# Sheet1.net
KiCad netlist of a schematic drawn in Altium Designer
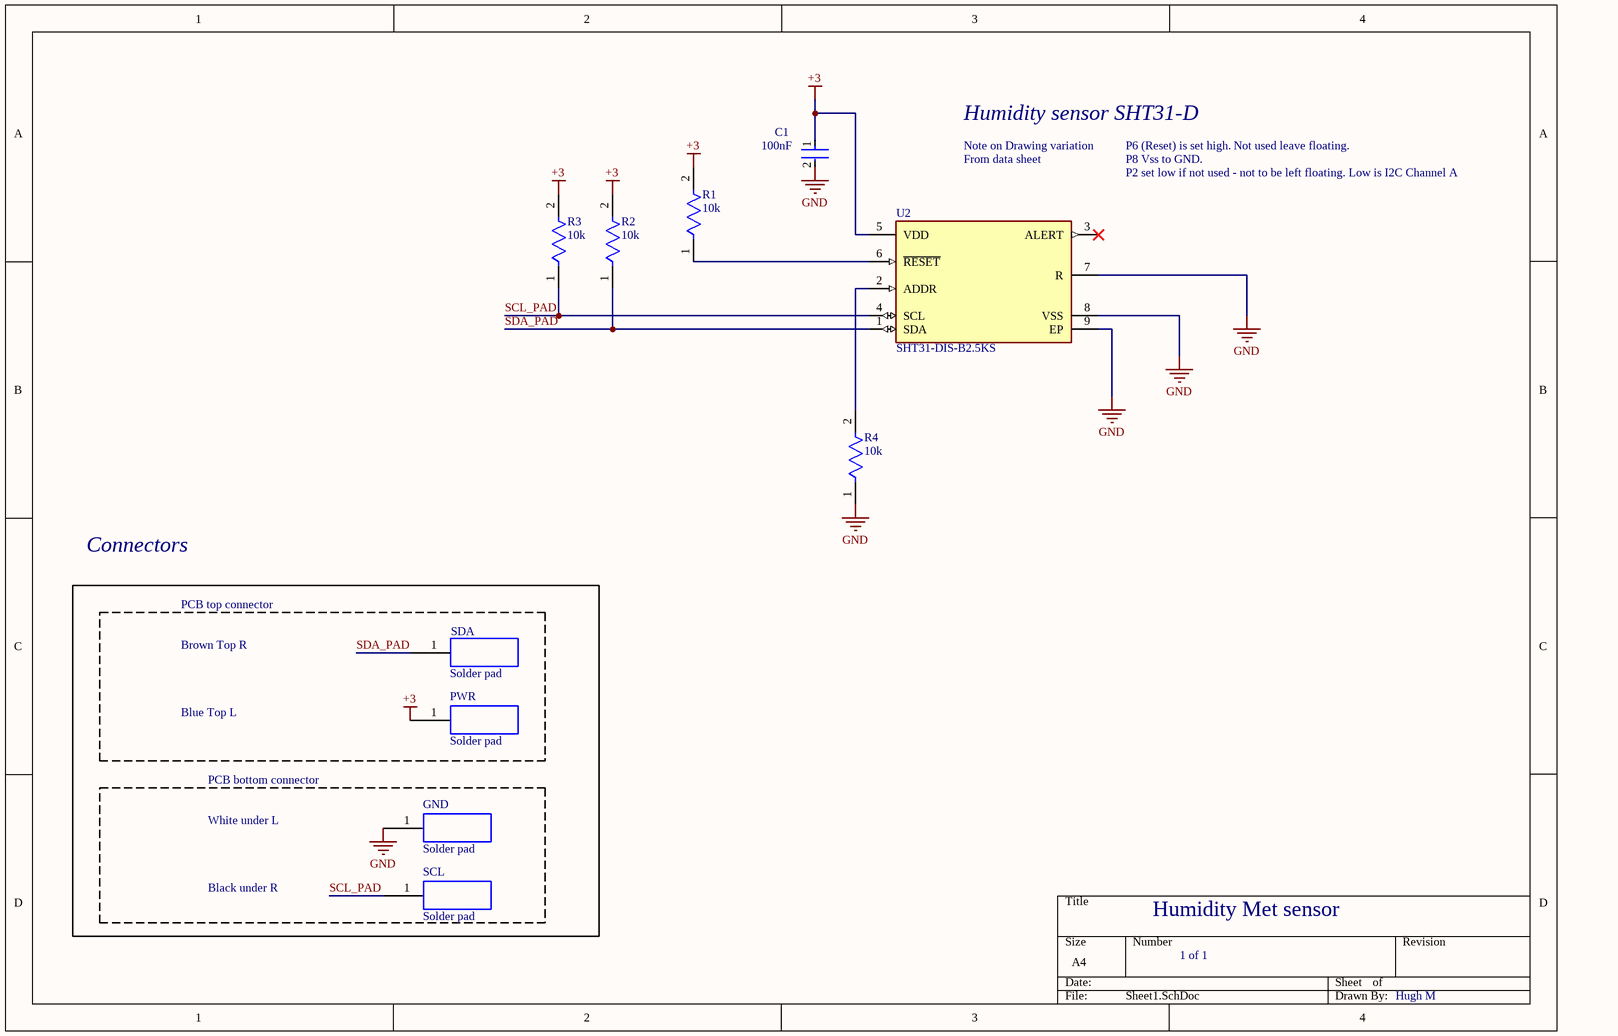
[diagram p0: Sheet1.SchDoc]

(export (version "E")
  (design (tool "Eeschema 10.0.6"))
  (components
    (comp (ref "C1")
      (value "100nF")
      (footprint "FP-C0402-BB-MFG")
      (description "CAP CER 0.1UF 10V X5R 0402")
      (fields (field (name "MANUFACTURER") "Kemet") (field (name "TOLERANCE") "0.1"))
      (libsource (lib "Altium Content Vault") (part "b4654b650e69147ec39a6b967a45e02"))
    )
    (comp (ref "GND") (value "Solder pad") (footprint "pad") (libsource (lib "pad1") (part "pad")))
    (comp (ref "PWR") (value "Solder pad") (footprint "pad") (libsource (lib "pad1") (part "pad")))
    (comp (ref "R1")
      (value "10k")
      (footprint "FP-AC0402-MFG")
      (description "RES 10kΩ ±1% 0.063W 0402")
      (fields (field (name "TOLERANCE") "1%"))
      (libsource (lib "Altium Content Vault") (part "1029c3af85768c4190bb7ad29bc67b5"))
    )
    (comp (ref "R2")
      (value "10k")
      (footprint "FP-AC0402-MFG")
      (description "RES 10kΩ ±1% 0.063W 0402")
      (fields (field (name "TOLERANCE") "1%"))
      (libsource (lib "Altium Content Vault") (part "1029c3af85768c4190bb7ad29bc67b5"))
    )
    (comp (ref "R3")
      (value "10k")
      (footprint "FP-AC0402-MFG")
      (description "RES 10kΩ ±1% 0.063W 0402")
      (fields (field (name "TOLERANCE") "1%"))
      (libsource (lib "Altium Content Vault") (part "1029c3af85768c4190bb7ad29bc67b5"))
    )
    (comp (ref "R4")
      (value "10k")
      (footprint "FP-AC0402-MFG")
      (description "RES 10kΩ ±1% 0.063W 0402")
      (fields (field (name "TOLERANCE") "1%"))
      (libsource (lib "Altium Content Vault") (part "1029c3af85768c4190bb7ad29bc67b5"))
    )
    (comp (ref "SCL") (value "Solder pad") (footprint "pad") (libsource (lib "pad1") (part "pad")))
    (comp (ref "SDA") (value "Solder pad") (footprint "pad") (libsource (lib "pad1") (part "pad")))
    (comp (ref "U2")
      (value "SHT31-DIS-B2.5KS")
      (footprint "FP-SHT31-DIS-B2_5KS-MFG")
      (description "SENSOR HUMID/TEMP 5V I2C 2% SMD")
      (libsource (lib "Altium Content Vault") (part "666307a9354d2867b06523a408f450d"))
    )
  )
  (nets
    (net (code "1") (name "+3") (class "Default")
      (node (ref "C1") (pin "1") (pinfunction "1_1") (pintype "passive"))
      (node (ref "PWR") (pin "1") (pinfunction "1_1") (pintype "passive"))
      (node (ref "R1") (pin "2") (pinfunction "2_2") (pintype "passive"))
      (node (ref "R2") (pin "2") (pinfunction "2_2") (pintype "passive"))
      (node (ref "R3") (pin "2") (pinfunction "2_2") (pintype "passive"))
      (node (ref "U2") (pin "5") (pinfunction "VDD_5") (pintype "power_in"))
    )
    (net (code "2") (name "/SCL_PAD") (class "Default")
      (node (ref "R3") (pin "1") (pinfunction "1_1") (pintype "passive"))
      (node (ref "SCL") (pin "1") (pinfunction "1_1") (pintype "passive"))
      (node (ref "U2") (pin "4") (pinfunction "SCL_4") (pintype "bidirectional"))
    )
    (net (code "3") (name "/SDA_PAD") (class "Default")
      (node (ref "R2") (pin "1") (pinfunction "1_1") (pintype "passive"))
      (node (ref "SDA") (pin "1") (pinfunction "1_1") (pintype "passive"))
      (node (ref "U2") (pin "1") (pinfunction "SDA_1") (pintype "bidirectional"))
    )
    (net (code "4") (name "GND") (class "Default")
      (node (ref "C1") (pin "2") (pinfunction "2_2") (pintype "passive"))
      (node (ref "GND") (pin "1") (pinfunction "1_1") (pintype "passive"))
      (node (ref "R4") (pin "1") (pinfunction "1_1") (pintype "passive"))
      (node (ref "U2") (pin "7") (pinfunction "R_7") (pintype "passive"))
      (node (ref "U2") (pin "8") (pinfunction "VSS_8") (pintype "power_in"))
      (node (ref "U2") (pin "9") (pinfunction "EP_9") (pintype "power_in"))
    )
    (net (code "5") (name "Net-(U2-ADDR)") (class "Default")
      (node (ref "R4") (pin "2") (pinfunction "2_2") (pintype "passive"))
      (node (ref "U2") (pin "2") (pinfunction "ADDR_2") (pintype "input"))
    )
    (net (code "6") (name "Net-(U2-~{RESET})") (class "Default")
      (node (ref "R1") (pin "1") (pinfunction "1_1") (pintype "passive"))
      (node (ref "U2") (pin "6") (pinfunction "~{RESET}_6") (pintype "input"))
    )
    (net (code "7") (name "unconnected-(U2-ALERT-Pad3)") (class "Default")
      (node (ref "U2") (pin "3") (pinfunction "ALERT_3") (pintype "output+no_connect"))
    )
  )
)
